# mbed_sonar.net
KiCad netlist of a schematic drawn in EAGLE
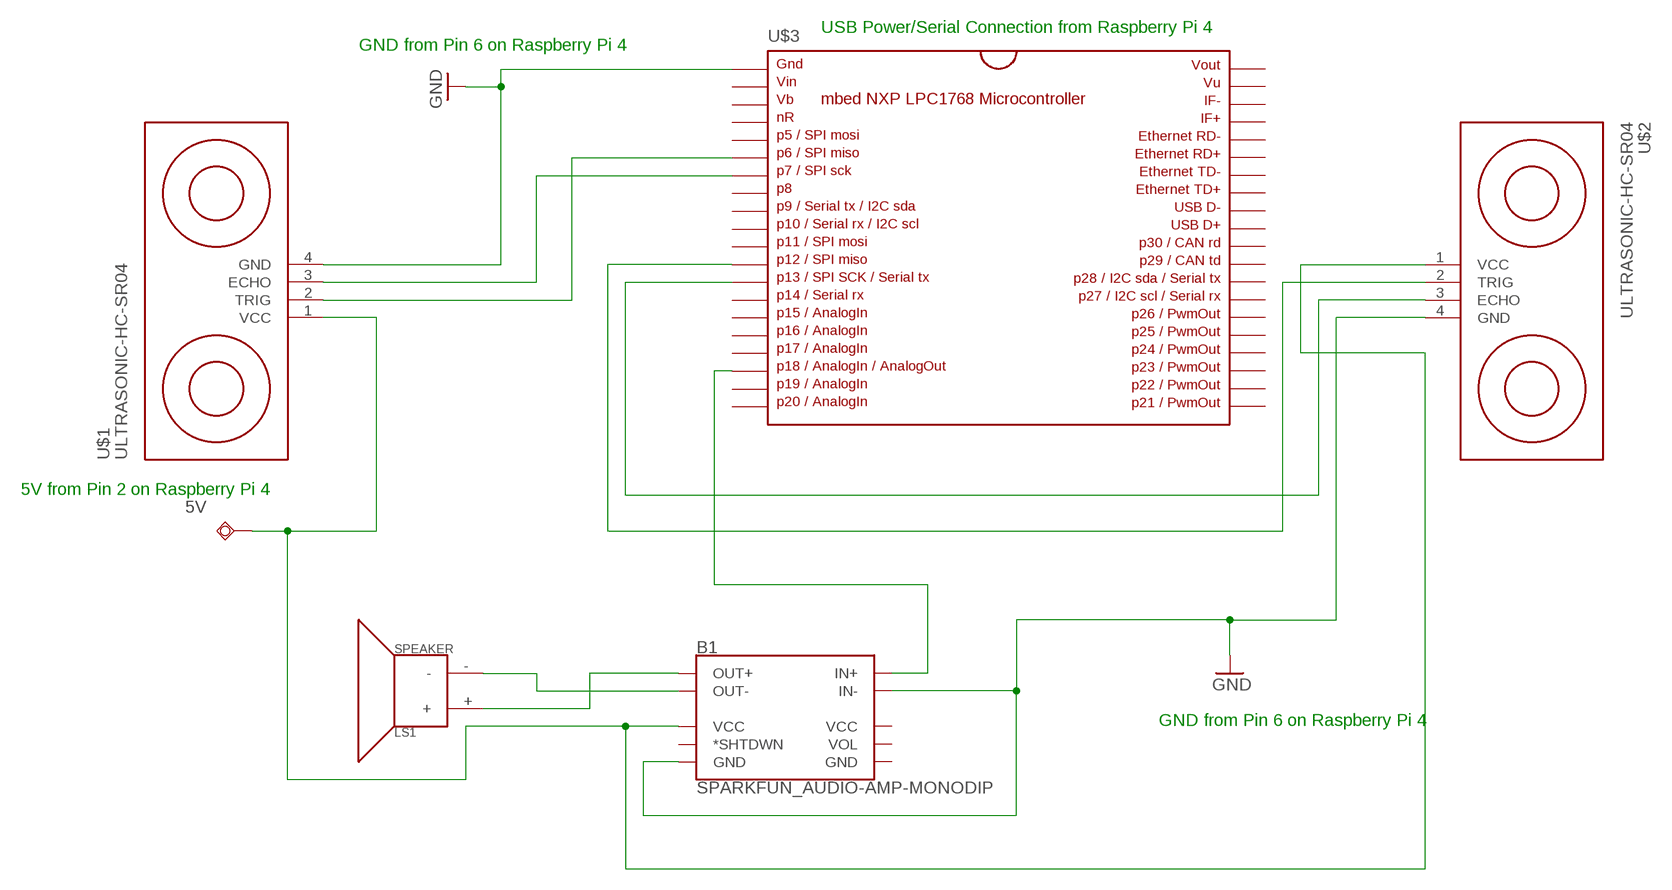
[diagram p0: schematic, sheet 1]

(export (version "E")
  (design (tool "Eeschema 10.0.6"))
  (components
    (comp (ref "5V")
      (value "TPSQPAD1-20")
      (footprint "eagle-import:P1-20")
      (libsource (lib "eagle-import") (part "TPSQPAD1-20"))
    )
    (comp (ref "B1")
      (value "SPARKFUN_AUDIO-AMP-MONODIP")
      (footprint "eagle-import:AUDIO-AMP-MONO")
      (libsource (lib "eagle-import") (part "SPARKFUN_AUDIO-AMP-MONODIP"))
    )
    (comp (ref "LS1")
      (value "SPEAKER")
      (footprint "eagle-import:PCB_MOUNT_SPEAKER")
      (libsource (lib "eagle-import") (part "SPEAKER"))
    )
    (comp (ref "U$1")
      (value "ULTRASONIC-HC-SR04")
      (footprint "eagle-import:ULTRASONIC-HC-SR04")
      (libsource (lib "eagle-import") (part "ULTRASONIC-HC-SR04"))
    )
    (comp (ref "U$2")
      (value "ULTRASONIC-HC-SR04")
      (footprint "eagle-import:ULTRASONIC-HC-SR04")
      (libsource (lib "eagle-import") (part "ULTRASONIC-HC-SR04"))
    )
    (comp (ref "U$3")
      (value "MBED1768")
      (footprint "eagle-import:DIL40_0.9")
      (libsource (lib "eagle-import") (part "MBED_NXP_LPC1768"))
    )
  )
  (nets
    (net (code "1") (name "GND") (class "Default")
      (node (ref "B1") (pin "IN-") (pinfunction "IN-_IN-") (pintype "bidirectional"))
      (node (ref "B1") (pin "PWR-") (pinfunction "GND_PWR-") (pintype "bidirectional"))
      (node (ref "U$1") (pin "4") (pinfunction "GND_4") (pintype "power_in"))
      (node (ref "U$2") (pin "4") (pinfunction "GND_4") (pintype "power_in"))
      (node (ref "U$3") (pin "1") (pinfunction "P$1_1") (pintype "bidirectional"))
    )
    (net (code "2") (name "Net-(B1-PadOUT+)") (class "Default")
      (node (ref "B1") (pin "OUT+") (pinfunction "OUT+_OUT+") (pintype "bidirectional"))
      (node (ref "LS1") (pin "+") (pinfunction "+_+") (pintype "bidirectional"))
    )
    (net (code "3") (name "Net-(B1-PadOUT-)") (class "Default")
      (node (ref "B1") (pin "OUT-") (pinfunction "OUT-_OUT-") (pintype "bidirectional"))
      (node (ref "LS1") (pin "-") (pinfunction "-_-") (pintype "bidirectional"))
    )
    (net (code "4") (name "Net-(U$1-ECHO)") (class "Default")
      (node (ref "U$1") (pin "3") (pinfunction "ECHO_3") (pintype "output"))
      (node (ref "U$3") (pin "7") (pinfunction "P$7_7") (pintype "bidirectional"))
    )
    (net (code "5") (name "Net-(U$1-TRIG)") (class "Default")
      (node (ref "U$1") (pin "2") (pinfunction "TRIG_2") (pintype "input"))
      (node (ref "U$3") (pin "6") (pinfunction "P$6_6") (pintype "bidirectional"))
    )
    (net (code "6") (name "Net-(U$1-VCC)") (class "Default")
      (node (ref "5V") (pin "TP") (pinfunction "TP_TP") (pintype "input"))
      (node (ref "B1") (pin "PWR+") (pinfunction "VCC_PWR+") (pintype "bidirectional"))
      (node (ref "U$1") (pin "1") (pinfunction "VCC_1") (pintype "power_in"))
      (node (ref "U$2") (pin "1") (pinfunction "VCC_1") (pintype "power_in"))
    )
    (net (code "7") (name "Net-(U$2-ECHO)") (class "Default")
      (node (ref "U$2") (pin "3") (pinfunction "ECHO_3") (pintype "output"))
      (node (ref "U$3") (pin "13") (pinfunction "P$13_13") (pintype "bidirectional"))
    )
    (net (code "8") (name "Net-(U$2-TRIG)") (class "Default")
      (node (ref "U$2") (pin "2") (pinfunction "TRIG_2") (pintype "input"))
      (node (ref "U$3") (pin "12") (pinfunction "P$12_12") (pintype "bidirectional"))
    )
    (net (code "9") (name "Net-(U$3-P$18)") (class "Default")
      (node (ref "B1") (pin "IN+") (pinfunction "IN+_IN+") (pintype "bidirectional"))
      (node (ref "U$3") (pin "18") (pinfunction "P$18_18") (pintype "bidirectional"))
    )
    (net (code "10") (name "unconnected-(B1-*SHTDWN-PadS)") (class "Default")
      (node (ref "B1") (pin "S") (pinfunction "*SHTDWN_S") (pintype "bidirectional"))
    )
    (net (code "11") (name "unconnected-(B1-GND-PadVOL-)") (class "Default")
      (node (ref "B1") (pin "VOL-") (pinfunction "GND_VOL-") (pintype "bidirectional"))
    )
    (net (code "12") (name "unconnected-(B1-PadVOL)") (class "Default")
      (node (ref "B1") (pin "VOL") (pinfunction "VOL_VOL") (pintype "bidirectional"))
    )
    (net (code "13") (name "unconnected-(B1-VCC-PadVOL+)") (class "Default")
      (node (ref "B1") (pin "VOL+") (pinfunction "VCC_VOL+") (pintype "bidirectional"))
    )
    (net (code "14") (name "unconnected-(U$3-P$2-Pad2)") (class "Default")
      (node (ref "U$3") (pin "2") (pinfunction "P$2_2") (pintype "bidirectional"))
    )
    (net (code "15") (name "unconnected-(U$3-P$3-Pad3)") (class "Default")
      (node (ref "U$3") (pin "3") (pinfunction "P$3_3") (pintype "bidirectional"))
    )
    (net (code "16") (name "unconnected-(U$3-P$4-Pad4)") (class "Default")
      (node (ref "U$3") (pin "4") (pinfunction "P$4_4") (pintype "bidirectional"))
    )
    (net (code "17") (name "unconnected-(U$3-P$5-Pad5)") (class "Default")
      (node (ref "U$3") (pin "5") (pinfunction "P$5_5") (pintype "bidirectional"))
    )
    (net (code "18") (name "unconnected-(U$3-P$8-Pad8)") (class "Default")
      (node (ref "U$3") (pin "8") (pinfunction "P$8_8") (pintype "bidirectional"))
    )
    (net (code "19") (name "unconnected-(U$3-P$9-Pad9)") (class "Default")
      (node (ref "U$3") (pin "9") (pinfunction "P$9_9") (pintype "bidirectional"))
    )
    (net (code "20") (name "unconnected-(U$3-P$10-Pad10)") (class "Default")
      (node (ref "U$3") (pin "10") (pinfunction "P$10_10") (pintype "bidirectional"))
    )
    (net (code "21") (name "unconnected-(U$3-P$11-Pad11)") (class "Default")
      (node (ref "U$3") (pin "11") (pinfunction "P$11_11") (pintype "bidirectional"))
    )
    (net (code "22") (name "unconnected-(U$3-P$14-Pad14)") (class "Default")
      (node (ref "U$3") (pin "14") (pinfunction "P$14_14") (pintype "bidirectional"))
    )
    (net (code "23") (name "unconnected-(U$3-P$15-Pad15)") (class "Default")
      (node (ref "U$3") (pin "15") (pinfunction "P$15_15") (pintype "bidirectional"))
    )
    (net (code "24") (name "unconnected-(U$3-P$16-Pad16)") (class "Default")
      (node (ref "U$3") (pin "16") (pinfunction "P$16_16") (pintype "bidirectional"))
    )
    (net (code "25") (name "unconnected-(U$3-P$17-Pad17)") (class "Default")
      (node (ref "U$3") (pin "17") (pinfunction "P$17_17") (pintype "bidirectional"))
    )
    (net (code "26") (name "unconnected-(U$3-P$19-Pad19)") (class "Default")
      (node (ref "U$3") (pin "19") (pinfunction "P$19_19") (pintype "bidirectional"))
    )
    (net (code "27") (name "unconnected-(U$3-P$20-Pad20)") (class "Default")
      (node (ref "U$3") (pin "20") (pinfunction "P$20_20") (pintype "bidirectional"))
    )
    (net (code "28") (name "unconnected-(U$3-P$21-Pad21)") (class "Default")
      (node (ref "U$3") (pin "21") (pinfunction "P$21_21") (pintype "bidirectional"))
    )
    (net (code "29") (name "unconnected-(U$3-P$22-Pad22)") (class "Default")
      (node (ref "U$3") (pin "22") (pinfunction "P$22_22") (pintype "bidirectional"))
    )
    (net (code "30") (name "unconnected-(U$3-P$23-Pad23)") (class "Default")
      (node (ref "U$3") (pin "23") (pinfunction "P$23_23") (pintype "bidirectional"))
    )
    (net (code "31") (name "unconnected-(U$3-P$24-Pad24)") (class "Default")
      (node (ref "U$3") (pin "24") (pinfunction "P$24_24") (pintype "bidirectional"))
    )
    (net (code "32") (name "unconnected-(U$3-P$25-Pad25)") (class "Default")
      (node (ref "U$3") (pin "25") (pinfunction "P$25_25") (pintype "bidirectional"))
    )
    (net (code "33") (name "unconnected-(U$3-P$26-Pad26)") (class "Default")
      (node (ref "U$3") (pin "26") (pinfunction "P$26_26") (pintype "bidirectional"))
    )
    (net (code "34") (name "unconnected-(U$3-P$27-Pad27)") (class "Default")
      (node (ref "U$3") (pin "27") (pinfunction "P$27_27") (pintype "bidirectional"))
    )
    (net (code "35") (name "unconnected-(U$3-P$28-Pad28)") (class "Default")
      (node (ref "U$3") (pin "28") (pinfunction "P$28_28") (pintype "bidirectional"))
    )
    (net (code "36") (name "unconnected-(U$3-P$29-Pad29)") (class "Default")
      (node (ref "U$3") (pin "29") (pinfunction "P$29_29") (pintype "bidirectional"))
    )
    (net (code "37") (name "unconnected-(U$3-P$30-Pad30)") (class "Default")
      (node (ref "U$3") (pin "30") (pinfunction "P$30_30") (pintype "bidirectional"))
    )
    (net (code "38") (name "unconnected-(U$3-P$31-Pad31)") (class "Default")
      (node (ref "U$3") (pin "31") (pinfunction "P$31_31") (pintype "bidirectional"))
    )
    (net (code "39") (name "unconnected-(U$3-P$32-Pad32)") (class "Default")
      (node (ref "U$3") (pin "32") (pinfunction "P$32_32") (pintype "bidirectional"))
    )
    (net (code "40") (name "unconnected-(U$3-P$33-Pad33)") (class "Default")
      (node (ref "U$3") (pin "33") (pinfunction "P$33_33") (pintype "bidirectional"))
    )
    (net (code "41") (name "unconnected-(U$3-P$34-Pad34)") (class "Default")
      (node (ref "U$3") (pin "34") (pinfunction "P$34_34") (pintype "bidirectional"))
    )
    (net (code "42") (name "unconnected-(U$3-P$35-Pad35)") (class "Default")
      (node (ref "U$3") (pin "35") (pinfunction "P$35_35") (pintype "bidirectional"))
    )
    (net (code "43") (name "unconnected-(U$3-P$36-Pad36)") (class "Default")
      (node (ref "U$3") (pin "36") (pinfunction "P$36_36") (pintype "bidirectional"))
    )
    (net (code "44") (name "unconnected-(U$3-P$37-Pad37)") (class "Default")
      (node (ref "U$3") (pin "37") (pinfunction "P$37_37") (pintype "bidirectional"))
    )
    (net (code "45") (name "unconnected-(U$3-P$38-Pad38)") (class "Default")
      (node (ref "U$3") (pin "38") (pinfunction "P$38_38") (pintype "bidirectional"))
    )
    (net (code "46") (name "unconnected-(U$3-P$39-Pad39)") (class "Default")
      (node (ref "U$3") (pin "39") (pinfunction "P$39_39") (pintype "bidirectional"))
    )
    (net (code "47") (name "unconnected-(U$3-P$40-Pad40)") (class "Default")
      (node (ref "U$3") (pin "40") (pinfunction "P$40_40") (pintype "bidirectional"))
    )
  )
)
